# Nixie_PSU.net
KiCad netlist of a schematic drawn in Altium Designer
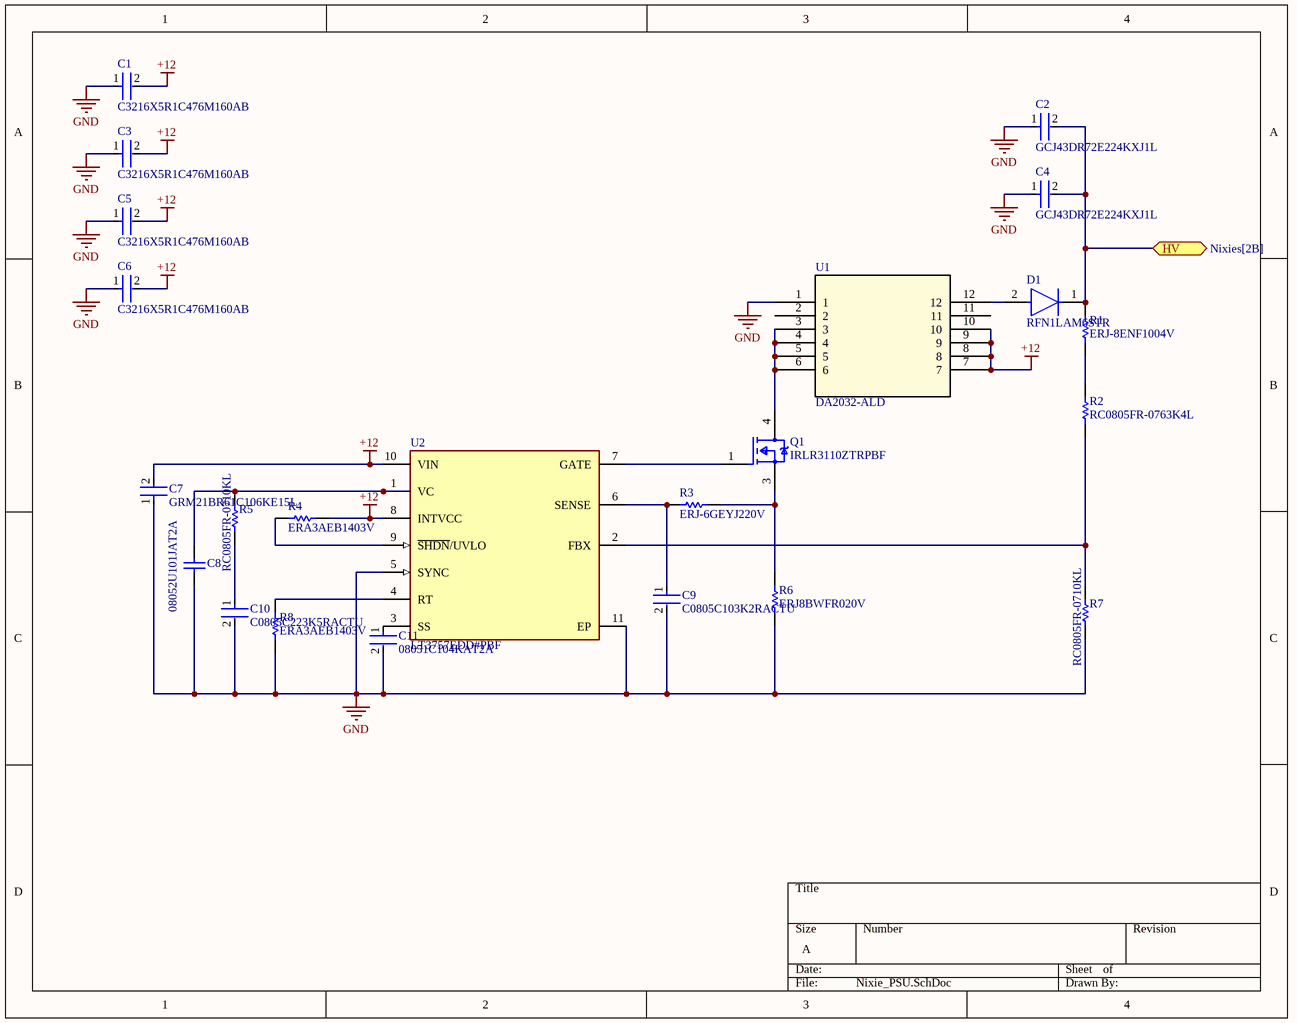
[diagram p0: Nixie_PSU.SchDoc]

(export (version "E")
  (design (tool "Eeschema 10.0.6"))
  (components
    (comp (ref "C1")
      (value "C3216X5R1C476M160AB")
      (footprint "FP-C3216-160-0_2-MFG")
      (description "Multilayer Ceramic Capacitors 47uF ±20% 16V X5R SMD 1206")
      (fields (field (name "TOLERANCE") "20%"))
      (libsource (lib "Altium Content Vault") (part "11868f565c42a9108669ba33697ecf6"))
    )
    (comp (ref "C2")
      (value "GCJ43DR72E224KXJ1L")
      (footprint "FP-GCJ43D-0_4-IPC_C")
      (description "0.22uF ±10% 250V Ceramic Capacitor X7R 1812 (4532 Metric)")
      (fields (field (name "TOLERANCE") "10%"))
      (libsource (lib "Altium Content Vault") (part "b4654b650e69147ec39a6b967a45e02"))
    )
    (comp (ref "C3")
      (value "C3216X5R1C476M160AB")
      (footprint "FP-C3216-160-0_2-MFG")
      (description "Multilayer Ceramic Capacitors 47uF ±20% 16V X5R SMD 1206")
      (fields (field (name "TOLERANCE") "20%"))
      (libsource (lib "Altium Content Vault") (part "11868f565c42a9108669ba33697ecf6"))
    )
    (comp (ref "C4")
      (value "GCJ43DR72E224KXJ1L")
      (footprint "FP-GCJ43D-0_4-IPC_C")
      (description "0.22uF ±10% 250V Ceramic Capacitor X7R 1812 (4532 Metric)")
      (fields (field (name "TOLERANCE") "10%"))
      (libsource (lib "Altium Content Vault") (part "b4654b650e69147ec39a6b967a45e02"))
    )
    (comp (ref "C5")
      (value "C3216X5R1C476M160AB")
      (footprint "FP-C3216-160-0_2-MFG")
      (description "Multilayer Ceramic Capacitors 47uF ±20% 16V X5R SMD 1206")
      (fields (field (name "TOLERANCE") "20%"))
      (libsource (lib "Altium Content Vault") (part "11868f565c42a9108669ba33697ecf6"))
    )
    (comp (ref "C6")
      (value "C3216X5R1C476M160AB")
      (footprint "FP-C3216-160-0_2-MFG")
      (description "Multilayer Ceramic Capacitors 47uF ±20% 16V X5R SMD 1206")
      (fields (field (name "TOLERANCE") "20%"))
      (libsource (lib "Altium Content Vault") (part "11868f565c42a9108669ba33697ecf6"))
    )
    (comp (ref "C7")
      (value "GRM21BR61C106KE15L")
      (footprint "FP-GRM21B-0_1-IPC_C")
      (description "Chip Multilayer Ceramic Capacitors for General Purpose, 0805, 10uF, X5R, 15%, 10%, 16V")
      (fields (field (name "TOLERANCE") "10%") (field (name "VOLTAGE") "16V"))
      (libsource (lib "Altium Content Vault") (part "b4654b650e69147ec39a6b967a45e02"))
    )
    (comp (ref "C8")
      (value "08052U101JAT2A")
      (footprint "CAPC2013X115X51ML20T26")
      (fields (field (name "MANUFACTURER") "AVX Interconnect / Elco"))
      (libsource (lib "Altium Content Vault") (part "CAP"))
    )
    (comp (ref "C9")
      (value "C0805C103K2RACTU")
      (footprint "FP-C0805C-DN-MFG")
      (description "CAP CER 10000PF 200V X7R 0805")
      (fields
        (field (name "OCTOPART") "https://octopart.com/c0805c103k2ractu-kemet-9138347")
        (field (name "TOLERANCE") "0.1")
      )
      (libsource (lib "Altium Content Vault") (part "b4654b650e69147ec39a6b967a45e02"))
    )
    (comp (ref "C10")
      (value "C0805C223K5RACTU")
      (footprint "FP-C0805C-DN-MFG")
      (description "CAP CER 0.022UF 50V X7R 0805")
      (fields
        (field (name "MANUFACTURER") "KEMET")
        (field (name "OCTOPART") "https://octopart.com/c0805c223k5ractu-kemet-145968")
      )
      (libsource (lib "Altium Content Vault") (part "b4654b650e69147ec39a6b967a45e02"))
    )
    (comp (ref "C11")
      (value "08051C104KAT2A")
      (footprint "FP-0805-L_2_01_0_2-W_1_25-IPC_B")
      (description "General Purpose Ceramic Capacitor, 0805, 100nF, 10%, X7R, 15%, 100V")
      (fields (field (name "VOLTAGE") "100V") (field (name "TOLERANCE") "10%"))
      (libsource (lib "Altium Content Vault") (part "b4654b650e69147ec39a6b967a45e02"))
    )
    (comp (ref "D1")
      (value "RFN1LAM6STR")
      (footprint "FP-PMDTM-MFG")
      (description "DIODE GEN PURP 600V 800MA PMDTM")
      (fields
        (field (name "OCTOPART") "https://octopart.com/rfn1lam6str-rohm-81877486")
        (field (name "MANUFACTURER") "Rohm")
      )
      (libsource (lib "Altium Content Vault") (part "d7152d700b627762746794eb795d46e"))
    )
    (comp (ref "Q1")
      (value "IRLR3110ZTRPBF")
      (footprint "FP-PG-TO252-3-MFG")
      (description "MOSFET N-CH 100V 42A DPAK")
      (fields
        (field (name "MANUFACTURER") "Infineon")
        (field (name "OCTOPART") "https://octopart.com/irlr3110ztrpbf-infineon-65875028")
      )
      (libsource (lib "Altium Content Vault") (part "1b46a229e508186a6fec6a11ed6f67e"))
    )
    (comp (ref "R1")
      (value "ERJ-8ENF1004V")
      (footprint "RESC3216X70X50NL05T20")
      (fields (field (name "MANUFACTURER") "Panasonic"))
      (libsource (lib "Altium Content Vault") (part "RES"))
    )
    (comp (ref "R2")
      (value "RC0805FR-0763K4L")
      (footprint "RESC2013X60X35NL10T20")
      (fields (field (name "MANUFACTURER") "Yageo"))
      (libsource (lib "Altium Content Vault") (part "RES"))
    )
    (comp (ref "R3")
      (value "ERJ-6GEYJ220V")
      (footprint "RESC2013X70X40ML20T20")
      (fields (field (name "MANUFACTURER") "Panasonic"))
      (libsource (lib "Altium Content Vault") (part "RES"))
    )
    (comp (ref "R4")
      (value "ERA3AEB1403V")
      (footprint "RESC1608X55X30LL20T20")
      (fields (field (name "MANUFACTURER") "Panasonic"))
      (libsource (lib "Altium Content Vault") (part "RES"))
    )
    (comp (ref "R5")
      (value "RC0805FR-0710KL")
      (footprint "RESC2013X60X35NL10T20")
      (description "Chip Resistor, 10 KOhm, +/- 1%, 0.125 W, -55 to 155 degC, 0805 (2012 Metric), RoHS, Tape and Reel")
      (fields (field (name "MANUFACTURER") "Yageo"))
      (libsource (lib "Altium Content Vault") (part "RES-2"))
    )
    (comp (ref "R6")
      (value "ERJ8BWFR020V")
      (footprint "RESC3216X70X50LL05T20")
      (fields (field (name "MANUFACTURER") "Panasonic"))
      (libsource (lib "Altium Content Vault") (part "RES"))
    )
    (comp (ref "R7")
      (value "RC0805FR-0710KL")
      (footprint "RESC2013X60X35NL10T20")
      (description "Chip Resistor, 10 KOhm, +/- 1%, 0.125 W, -55 to 155 degC, 0805 (2012 Metric), RoHS, Tape and Reel")
      (fields (field (name "MANUFACTURER") "Yageo"))
      (libsource (lib "Altium Content Vault") (part "RES-2"))
    )
    (comp (ref "R8")
      (value "ERA3AEB1403V")
      (footprint "RESC1608X55X30LL20T20")
      (fields (field (name "MANUFACTURER") "Panasonic"))
      (libsource (lib "Altium Content Vault") (part "RES"))
    )
    (comp (ref "U1")
      (value "DA2032-ALD")
      (footprint "SOIC12_LT3750_DA2032_14P98X17P2_COC")
      (description "No Description Available")
      (libsource (lib "Purdue University") (part "DA2032-ALD"))
    )
    (comp (ref "U2")
      (value "LT3757EDD#PBF")
      (footprint "FP-DD-10-05-08-1699-IPC_A")
      (description "IC REG CTRLR MULT TOPOLOGY 10DFN")
      (libsource (lib "Altium Content Vault") (part "87a5bb1a14c5d2e6336e4797f0f1323"))
    )
  )
  (nets
    (net (code "1") (name "+12") (class "Default")
      (node (ref "C1") (pin "2") (pinfunction "2_2") (pintype "passive"))
      (node (ref "C3") (pin "2") (pinfunction "2_2") (pintype "passive"))
      (node (ref "C5") (pin "2") (pinfunction "2_2") (pintype "passive"))
      (node (ref "C6") (pin "2") (pinfunction "2_2") (pintype "passive"))
      (node (ref "C7") (pin "2") (pinfunction "2_2") (pintype "passive"))
      (node (ref "R4") (pin "1") (pinfunction "1_1") (pintype "passive"))
      (node (ref "U1") (pin "10") (pinfunction "10_10") (pintype "passive"))
      (node (ref "U1") (pin "7") (pinfunction "7_7") (pintype "passive"))
      (node (ref "U1") (pin "8") (pinfunction "8_8") (pintype "passive"))
      (node (ref "U1") (pin "9") (pinfunction "9_9") (pintype "passive"))
      (node (ref "U2") (pin "10") (pinfunction "VIN_10") (pintype "power_in"))
      (node (ref "U2") (pin "8") (pinfunction "INTVCC_8") (pintype "power_in"))
    )
    (net (code "2") (name "/HV") (class "Default")
      (node (ref "C2") (pin "2") (pinfunction "2_2") (pintype "passive"))
      (node (ref "C4") (pin "2") (pinfunction "2_2") (pintype "passive"))
      (node (ref "D1") (pin "1") (pinfunction "C_1") (pintype "passive"))
      (node (ref "R1") (pin "2") (pinfunction "2_2") (pintype "passive"))
    )
    (net (code "3") (name "GND") (class "Default")
      (node (ref "C1") (pin "1") (pinfunction "1_1") (pintype "passive"))
      (node (ref "C10") (pin "2") (pinfunction "2_2") (pintype "passive"))
      (node (ref "C11") (pin "2") (pinfunction "2_2") (pintype "passive"))
      (node (ref "C2") (pin "1") (pinfunction "1_1") (pintype "passive"))
      (node (ref "C3") (pin "1") (pinfunction "1_1") (pintype "passive"))
      (node (ref "C4") (pin "1") (pinfunction "1_1") (pintype "passive"))
      (node (ref "C5") (pin "1") (pinfunction "1_1") (pintype "passive"))
      (node (ref "C6") (pin "1") (pinfunction "1_1") (pintype "passive"))
      (node (ref "C7") (pin "1") (pinfunction "1_1") (pintype "passive"))
      (node (ref "C8") (pin "1") (pinfunction "1_1") (pintype "passive"))
      (node (ref "C9") (pin "2") (pinfunction "2_2") (pintype "passive"))
      (node (ref "R6") (pin "1") (pinfunction "1_1") (pintype "passive"))
      (node (ref "R7") (pin "1") (pinfunction "1_1") (pintype "passive"))
      (node (ref "R8") (pin "2") (pinfunction "2_2") (pintype "passive"))
      (node (ref "U1") (pin "1") (pinfunction "1_1") (pintype "passive"))
      (node (ref "U2") (pin "11") (pinfunction "EP_11") (pintype "power_in"))
      (node (ref "U2") (pin "5") (pinfunction "SYNC_5") (pintype "input"))
    )
    (net (code "4") (name "Net-(C10-Pad1)") (class "Default")
      (node (ref "C10") (pin "1") (pinfunction "1_1") (pintype "passive"))
      (node (ref "R5") (pin "1") (pinfunction "1_1") (pintype "passive"))
    )
    (net (code "5") (name "Net-(D1-A)") (class "Default")
      (node (ref "D1") (pin "2") (pinfunction "A_2") (pintype "passive"))
      (node (ref "U1") (pin "12") (pinfunction "12_12") (pintype "passive"))
    )
    (net (code "6") (name "Net-(Q1-D)") (class "Default")
      (node (ref "Q1") (pin "4") (pinfunction "D_4") (pintype "passive"))
      (node (ref "U1") (pin "3") (pinfunction "3_3") (pintype "passive"))
      (node (ref "U1") (pin "4") (pinfunction "4_4") (pintype "passive"))
      (node (ref "U1") (pin "5") (pinfunction "5_5") (pintype "passive"))
      (node (ref "U1") (pin "6") (pinfunction "6_6") (pintype "passive"))
    )
    (net (code "7") (name "Net-(Q1-G)") (class "Default")
      (node (ref "Q1") (pin "1") (pinfunction "G_1") (pintype "passive"))
      (node (ref "U2") (pin "7") (pinfunction "GATE_7") (pintype "passive"))
    )
    (net (code "8") (name "Net-(Q1-S)") (class "Default")
      (node (ref "Q1") (pin "3") (pinfunction "S_3") (pintype "passive"))
      (node (ref "R3") (pin "2") (pinfunction "2_2") (pintype "passive"))
      (node (ref "R6") (pin "2") (pinfunction "2_2") (pintype "passive"))
    )
    (net (code "9") (name "Net-(R1-Pad1)") (class "Default")
      (node (ref "R1") (pin "1") (pinfunction "1_1") (pintype "passive"))
      (node (ref "R2") (pin "2") (pinfunction "2_2") (pintype "passive"))
    )
    (net (code "10") (name "Net-(U2-FBX)") (class "Default")
      (node (ref "R2") (pin "1") (pinfunction "1_1") (pintype "passive"))
      (node (ref "R7") (pin "2") (pinfunction "2_2") (pintype "passive"))
      (node (ref "U2") (pin "2") (pinfunction "FBX_2") (pintype "passive"))
    )
    (net (code "11") (name "Net-(U2-RT)") (class "Default")
      (node (ref "R8") (pin "1") (pinfunction "1_1") (pintype "passive"))
      (node (ref "U2") (pin "4") (pinfunction "RT_4") (pintype "passive"))
    )
    (net (code "12") (name "Net-(U2-SENSE)") (class "Default")
      (node (ref "C9") (pin "1") (pinfunction "1_1") (pintype "passive"))
      (node (ref "R3") (pin "1") (pinfunction "1_1") (pintype "passive"))
      (node (ref "U2") (pin "6") (pinfunction "SENSE_6") (pintype "passive"))
    )
    (net (code "13") (name "Net-(U2-SS)") (class "Default")
      (node (ref "C11") (pin "1") (pinfunction "1_1") (pintype "passive"))
      (node (ref "U2") (pin "3") (pinfunction "SS_3") (pintype "passive"))
    )
    (net (code "14") (name "Net-(U2-VC)") (class "Default")
      (node (ref "C8") (pin "2") (pinfunction "2_2") (pintype "passive"))
      (node (ref "R5") (pin "2") (pinfunction "2_2") (pintype "passive"))
      (node (ref "U2") (pin "1") (pinfunction "VC_1") (pintype "passive"))
    )
    (net (code "15") (name "Net-(U2-~{SHDN}{slash}UVLO)") (class "Default")
      (node (ref "R4") (pin "2") (pinfunction "2_2") (pintype "passive"))
      (node (ref "U2") (pin "9") (pinfunction "~{SHDN}/UVLO_9") (pintype "input"))
    )
    (net (code "16") (name "unconnected-(U1-Pad2)") (class "Default")
      (node (ref "U1") (pin "2") (pinfunction "2_2") (pintype "passive"))
    )
    (net (code "17") (name "unconnected-(U1-Pad11)") (class "Default")
      (node (ref "U1") (pin "11") (pinfunction "11_11") (pintype "passive"))
    )
  )
)
